# new_design.net
KiCad netlist of a schematic drawn in EAGLE
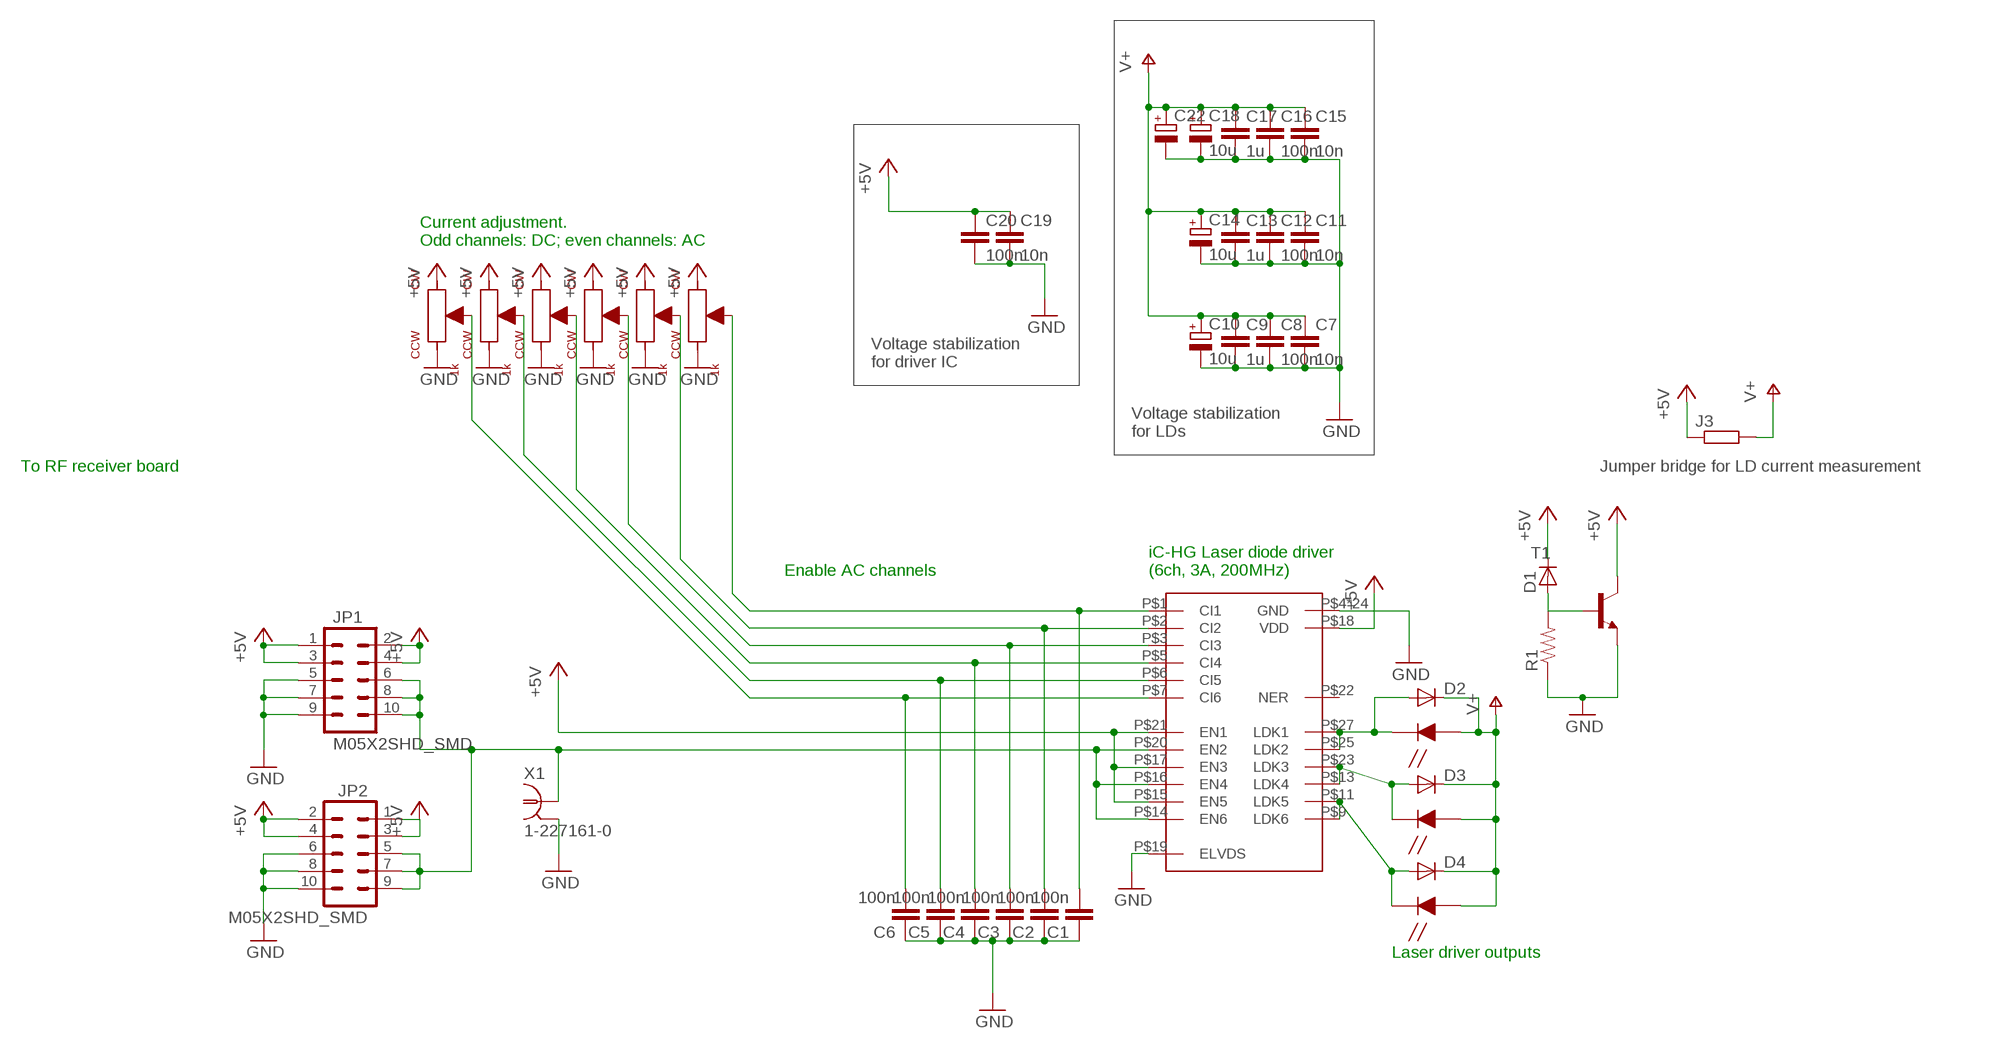
[diagram p0: schematic, sheet 1]

(export (version "E")
  (design (tool "Eeschema 10.0.6"))
  (components
    (comp (ref "C1")
      (value "100n")
      (footprint "eagle-import:C0402K")
      (libsource (lib "eagle-import") (part "C-EUC0402K"))
    )
    (comp (ref "C2")
      (value "100n")
      (footprint "eagle-import:C0402K")
      (libsource (lib "eagle-import") (part "C-EUC0402K"))
    )
    (comp (ref "C3")
      (value "100n")
      (footprint "eagle-import:C0402K")
      (libsource (lib "eagle-import") (part "C-EUC0402K"))
    )
    (comp (ref "C4")
      (value "100n")
      (footprint "eagle-import:C0402K")
      (libsource (lib "eagle-import") (part "C-EUC0402K"))
    )
    (comp (ref "C5")
      (value "100n")
      (footprint "eagle-import:C0402K")
      (libsource (lib "eagle-import") (part "C-EUC0402K"))
    )
    (comp (ref "C6")
      (value "100n")
      (footprint "eagle-import:C0402K")
      (libsource (lib "eagle-import") (part "C-EUC0402K"))
    )
    (comp (ref "C7")
      (value "10n")
      (footprint "eagle-import:C0402K")
      (libsource (lib "eagle-import") (part "C-EUC0402K"))
    )
    (comp (ref "C8")
      (value "100n")
      (footprint "eagle-import:C0402K")
      (libsource (lib "eagle-import") (part "C-EUC0402K"))
    )
    (comp (ref "C9")
      (value "1u")
      (footprint "eagle-import:C0603")
      (libsource (lib "eagle-import") (part "C-EUC0603"))
    )
    (comp (ref "C10")
      (value "10u")
      (footprint "eagle-import:SMC_B")
      (libsource (lib "eagle-import") (part "CPOL-EUSMCB"))
    )
    (comp (ref "C11")
      (value "10n")
      (footprint "eagle-import:C0402K")
      (libsource (lib "eagle-import") (part "C-EUC0402K"))
    )
    (comp (ref "C12")
      (value "100n")
      (footprint "eagle-import:C0402K")
      (libsource (lib "eagle-import") (part "C-EUC0402K"))
    )
    (comp (ref "C13")
      (value "1u")
      (footprint "eagle-import:C0603")
      (libsource (lib "eagle-import") (part "C-EUC0603"))
    )
    (comp (ref "C14")
      (value "10u")
      (footprint "eagle-import:SMC_B")
      (libsource (lib "eagle-import") (part "CPOL-EUSMCB"))
    )
    (comp (ref "C15")
      (value "10n")
      (footprint "eagle-import:C0402K")
      (libsource (lib "eagle-import") (part "C-EUC0402K"))
    )
    (comp (ref "C16")
      (value "100n")
      (footprint "eagle-import:C0402K")
      (libsource (lib "eagle-import") (part "C-EUC0402K"))
    )
    (comp (ref "C17")
      (value "1u")
      (footprint "eagle-import:C0603")
      (libsource (lib "eagle-import") (part "C-EUC0603"))
    )
    (comp (ref "C18")
      (value "10u")
      (footprint "eagle-import:SMC_B")
      (libsource (lib "eagle-import") (part "CPOL-EUSMCB"))
    )
    (comp (ref "C19")
      (value "10n")
      (footprint "eagle-import:C0402K")
      (libsource (lib "eagle-import") (part "C-EUC0402K"))
    )
    (comp (ref "C20")
      (value "100n")
      (footprint "eagle-import:C0402K")
      (libsource (lib "eagle-import") (part "C-EUC0402K"))
    )
    (comp (ref "C22")
      (value "CPOL-EUCT7343")
      (footprint "eagle-import:CT7343")
      (libsource (lib "eagle-import") (part "CPOL-EUCT7343"))
    )
    (comp (ref "D1")
      (value "D-SMB")
      (footprint "eagle-import:SMB")
      (libsource (lib "eagle-import") (part "D-SMB"))
    )
    (comp (ref "D2")
      (value "DIODE-SOD523")
      (footprint "eagle-import:SOD523")
      (libsource (lib "eagle-import") (part "DIODE-SOD523"))
    )
    (comp (ref "D3")
      (value "DIODE-SOD523")
      (footprint "eagle-import:SOD523")
      (libsource (lib "eagle-import") (part "DIODE-SOD523"))
    )
    (comp (ref "D4")
      (value "DIODE-SOD523")
      (footprint "eagle-import:SOD523")
      (libsource (lib "eagle-import") (part "DIODE-SOD523"))
    )
    (comp (ref "IC1")
      (value "IC-HGTHERMAL")
      (footprint "eagle-import:QFN28-PAD")
      (libsource (lib "eagle-import") (part "IC-HGTHERMAL"))
    )
    (comp (ref "J3")
      (value "R-EU_R1210")
      (footprint "eagle-import:R1210")
      (libsource (lib "eagle-import") (part "R-EU_R1210"))
    )
    (comp (ref "JP1")
      (value "M05X2SHD_SMD")
      (footprint "eagle-import:2X5-SHROUDED_SMD")
      (libsource (lib "eagle-import") (part "M05X2SHD_SMD"))
    )
    (comp (ref "JP2")
      (value "M05X2SHD_SMD")
      (footprint "eagle-import:2X5-SHROUDED_SMD")
      (libsource (lib "eagle-import") (part "M05X2SHD_SMD"))
    )
    (comp (ref "LD1")
      (value "LASER")
      (footprint "eagle-import:LD-FLAT")
      (libsource (lib "eagle-import") (part "LASER"))
    )
    (comp (ref "LD2")
      (value "LASER")
      (footprint "eagle-import:LD-FLAT")
      (libsource (lib "eagle-import") (part "LASER"))
    )
    (comp (ref "LD3")
      (value "LASER")
      (footprint "eagle-import:LD-FLAT")
      (libsource (lib "eagle-import") (part "LASER"))
    )
    (comp (ref "P1")
      (value "1k")
      (footprint "eagle-import:EVM-1D")
      (libsource (lib "eagle-import") (part "TRIMMERPANASONIC_EVM1D"))
    )
    (comp (ref "P2")
      (value "1k")
      (footprint "eagle-import:EVM-1D")
      (libsource (lib "eagle-import") (part "TRIMMERPANASONIC_EVM1D"))
    )
    (comp (ref "P3")
      (value "1k")
      (footprint "eagle-import:EVM-1D")
      (libsource (lib "eagle-import") (part "TRIMMERPANASONIC_EVM1D"))
    )
    (comp (ref "P4")
      (value "1k")
      (footprint "eagle-import:EVM-1D")
      (libsource (lib "eagle-import") (part "TRIMMERPANASONIC_EVM1D"))
    )
    (comp (ref "P5")
      (value "1k")
      (footprint "eagle-import:EVM-1D")
      (libsource (lib "eagle-import") (part "TRIMMERPANASONIC_EVM1D"))
    )
    (comp (ref "P6")
      (value "1k")
      (footprint "eagle-import:EVM-1D")
      (libsource (lib "eagle-import") (part "TRIMMERPANASONIC_EVM1D"))
    )
    (comp (ref "R1")
      (value "RESISTOR0805-RES")
      (footprint "eagle-import:0805")
      (libsource (lib "eagle-import") (part "RESISTOR0805-RES"))
    )
    (comp (ref "T1")
      (value "-NPN-SOT223")
      (footprint "eagle-import:SOT223")
      (libsource (lib "eagle-import") (part "-NPN-SOT223"))
    )
    (comp (ref "X1")
      (value "1-227161-0")
      (footprint "eagle-import:AMP_227161")
      (fields (field (name "MF") "TYCO ELECTRONICS") (field (name "MPN") "1-227161"))
      (libsource (lib "eagle-import") (part "?2271611--0"))
    )
  )
  (nets
    (net (code "1") (name "+5V") (class "Default")
      (node (ref "C19") (pin "1") (pinfunction "1_1") (pintype "passive"))
      (node (ref "C20") (pin "1") (pinfunction "1_1") (pintype "passive"))
      (node (ref "D1") (pin "1") (pinfunction "C_1") (pintype "passive"))
      (node (ref "IC1") (pin "P$15") (pinfunction "EN5_P$15") (pintype "input"))
      (node (ref "IC1") (pin "P$17") (pinfunction "EN3_P$17") (pintype "input"))
      (node (ref "IC1") (pin "P$18") (pinfunction "VDD_P$18") (pintype "power_in"))
      (node (ref "IC1") (pin "P$21") (pinfunction "EN1_P$21") (pintype "input"))
      (node (ref "J3") (pin "1") (pinfunction "1_1") (pintype "passive"))
      (node (ref "JP1") (pin "1") (pinfunction "1_1") (pintype "passive"))
      (node (ref "JP1") (pin "2") (pinfunction "2_2") (pintype "passive"))
      (node (ref "JP1") (pin "3") (pinfunction "3_3") (pintype "passive"))
      (node (ref "JP1") (pin "4") (pinfunction "4_4") (pintype "passive"))
      (node (ref "JP2") (pin "1") (pinfunction "1_1") (pintype "passive"))
      (node (ref "JP2") (pin "2") (pinfunction "2_2") (pintype "passive"))
      (node (ref "JP2") (pin "3") (pinfunction "3_3") (pintype "passive"))
      (node (ref "JP2") (pin "4") (pinfunction "4_4") (pintype "passive"))
      (node (ref "P1") (pin "CW") (pinfunction "CW_CW") (pintype "output"))
      (node (ref "P2") (pin "CW") (pinfunction "CW_CW") (pintype "output"))
      (node (ref "P3") (pin "CW") (pinfunction "CW_CW") (pintype "output"))
      (node (ref "P4") (pin "CW") (pinfunction "CW_CW") (pintype "output"))
      (node (ref "P5") (pin "CW") (pinfunction "CW_CW") (pintype "output"))
      (node (ref "P6") (pin "CW") (pinfunction "CW_CW") (pintype "output"))
      (node (ref "T1") (pin "4") (pinfunction "C_4") (pintype "passive"))
    )
    (net (code "2") (name "GND") (class "Default")
      (node (ref "C1") (pin "1") (pinfunction "1_1") (pintype "passive"))
      (node (ref "C10") (pin "-") (pinfunction "-_-") (pintype "passive"))
      (node (ref "C11") (pin "2") (pinfunction "2_2") (pintype "passive"))
      (node (ref "C12") (pin "2") (pinfunction "2_2") (pintype "passive"))
      (node (ref "C13") (pin "2") (pinfunction "2_2") (pintype "passive"))
      (node (ref "C14") (pin "-") (pinfunction "-_-") (pintype "passive"))
      (node (ref "C15") (pin "2") (pinfunction "2_2") (pintype "passive"))
      (node (ref "C16") (pin "2") (pinfunction "2_2") (pintype "passive"))
      (node (ref "C17") (pin "2") (pinfunction "2_2") (pintype "passive"))
      (node (ref "C18") (pin "-") (pinfunction "-_-") (pintype "passive"))
      (node (ref "C19") (pin "2") (pinfunction "2_2") (pintype "passive"))
      (node (ref "C2") (pin "1") (pinfunction "1_1") (pintype "passive"))
      (node (ref "C20") (pin "2") (pinfunction "2_2") (pintype "passive"))
      (node (ref "C22") (pin "-") (pinfunction "-_-") (pintype "passive"))
      (node (ref "C3") (pin "1") (pinfunction "1_1") (pintype "passive"))
      (node (ref "C4") (pin "1") (pinfunction "1_1") (pintype "passive"))
      (node (ref "C5") (pin "1") (pinfunction "1_1") (pintype "passive"))
      (node (ref "C6") (pin "1") (pinfunction "1_1") (pintype "passive"))
      (node (ref "C7") (pin "2") (pinfunction "2_2") (pintype "passive"))
      (node (ref "C8") (pin "2") (pinfunction "2_2") (pintype "passive"))
      (node (ref "C9") (pin "2") (pinfunction "2_2") (pintype "passive"))
      (node (ref "IC1") (pin "P$10") (pinfunction "GND_P$10") (pintype "power_in"))
      (node (ref "IC1") (pin "P$12") (pinfunction "GND_P$12") (pintype "power_in"))
      (node (ref "IC1") (pin "P$19") (pinfunction "ELVDS_P$19") (pintype "output"))
      (node (ref "IC1") (pin "P$24") (pinfunction "GND_P$24") (pintype "power_in"))
      (node (ref "IC1") (pin "P$26") (pinfunction "GND_P$26") (pintype "power_in"))
      (node (ref "IC1") (pin "P$28") (pinfunction "GND_P$28") (pintype "power_in"))
      (node (ref "IC1") (pin "P$29") (pinfunction "GND_P$29") (pintype "power_in"))
      (node (ref "IC1") (pin "P$30") (pinfunction "GND_P$30") (pintype "power_in"))
      (node (ref "IC1") (pin "P$31") (pinfunction "GND_P$31") (pintype "power_in"))
      (node (ref "IC1") (pin "P$32") (pinfunction "GND_P$32") (pintype "power_in"))
      (node (ref "IC1") (pin "P$33") (pinfunction "GND_P$33") (pintype "power_in"))
      (node (ref "IC1") (pin "P$34") (pinfunction "GND_P$34") (pintype "power_in"))
      (node (ref "IC1") (pin "P$35") (pinfunction "GND_P$35") (pintype "power_in"))
      (node (ref "IC1") (pin "P$36") (pinfunction "GND_P$36") (pintype "power_in"))
      (node (ref "IC1") (pin "P$37") (pinfunction "GND_P$37") (pintype "power_in"))
      (node (ref "IC1") (pin "P$38") (pinfunction "GND_P$38") (pintype "power_in"))
      (node (ref "IC1") (pin "P$39") (pinfunction "GND_P$39") (pintype "power_in"))
      (node (ref "IC1") (pin "P$4") (pinfunction "GND_P$4") (pintype "power_in"))
      (node (ref "IC1") (pin "P$40") (pinfunction "GND_P$40") (pintype "power_in"))
      (node (ref "IC1") (pin "P$41") (pinfunction "GND_P$41") (pintype "power_in"))
      (node (ref "IC1") (pin "P$42") (pinfunction "GND_P$42") (pintype "power_in"))
      (node (ref "IC1") (pin "P$43") (pinfunction "GND_P$43") (pintype "power_in"))
      (node (ref "IC1") (pin "P$44") (pinfunction "GND_P$44") (pintype "power_in"))
      (node (ref "IC1") (pin "P$45") (pinfunction "GND_P$45") (pintype "power_in"))
      (node (ref "IC1") (pin "P$8") (pinfunction "GND_P$8") (pintype "power_in"))
      (node (ref "JP1") (pin "5") (pinfunction "5_5") (pintype "passive"))
      (node (ref "JP1") (pin "7") (pinfunction "7_7") (pintype "passive"))
      (node (ref "JP1") (pin "9") (pinfunction "9_9") (pintype "passive"))
      (node (ref "JP2") (pin "10") (pinfunction "10_10") (pintype "passive"))
      (node (ref "JP2") (pin "6") (pinfunction "6_6") (pintype "passive"))
      (node (ref "JP2") (pin "8") (pinfunction "8_8") (pintype "passive"))
      (node (ref "P1") (pin "CCW") (pinfunction "CCW_CCW") (pintype "output"))
      (node (ref "P2") (pin "CCW") (pinfunction "CCW_CCW") (pintype "output"))
      (node (ref "P3") (pin "CCW") (pinfunction "CCW_CCW") (pintype "output"))
      (node (ref "P4") (pin "CCW") (pinfunction "CCW_CCW") (pintype "output"))
      (node (ref "P5") (pin "CCW") (pinfunction "CCW_CCW") (pintype "output"))
      (node (ref "P6") (pin "CCW") (pinfunction "CCW_CCW") (pintype "output"))
      (node (ref "R1") (pin "1") (pinfunction "1_1") (pintype "passive"))
      (node (ref "T1") (pin "3") (pinfunction "E_3") (pintype "passive"))
      (node (ref "X1") (pin "2") (pinfunction "2_2") (pintype "passive"))
    )
    (net (code "3") (name "Net-(D1-A)") (class "Default")
      (node (ref "D1") (pin "2") (pinfunction "A_2") (pintype "passive"))
      (node (ref "R1") (pin "2") (pinfunction "2_2") (pintype "passive"))
      (node (ref "T1") (pin "1") (pinfunction "B_1") (pintype "passive"))
    )
    (net (code "4") (name "Net-(IC1-CI1)") (class "Default")
      (node (ref "C1") (pin "2") (pinfunction "2_2") (pintype "passive"))
      (node (ref "IC1") (pin "P$1") (pinfunction "CI1_P$1") (pintype "input"))
      (node (ref "P1") (pin "W") (pinfunction "W_W") (pintype "output"))
    )
    (net (code "5") (name "Net-(IC1-CI2)") (class "Default")
      (node (ref "C2") (pin "2") (pinfunction "2_2") (pintype "passive"))
      (node (ref "IC1") (pin "P$2") (pinfunction "CI2_P$2") (pintype "input"))
      (node (ref "P2") (pin "W") (pinfunction "W_W") (pintype "output"))
    )
    (net (code "6") (name "Net-(IC1-CI3)") (class "Default")
      (node (ref "C3") (pin "2") (pinfunction "2_2") (pintype "passive"))
      (node (ref "IC1") (pin "P$3") (pinfunction "CI3_P$3") (pintype "input"))
      (node (ref "P3") (pin "W") (pinfunction "W_W") (pintype "output"))
    )
    (net (code "7") (name "Net-(IC1-CI4)") (class "Default")
      (node (ref "C4") (pin "2") (pinfunction "2_2") (pintype "passive"))
      (node (ref "IC1") (pin "P$5") (pinfunction "CI4_P$5") (pintype "input"))
      (node (ref "P4") (pin "W") (pinfunction "W_W") (pintype "output"))
    )
    (net (code "8") (name "Net-(IC1-CI5)") (class "Default")
      (node (ref "C5") (pin "2") (pinfunction "2_2") (pintype "passive"))
      (node (ref "IC1") (pin "P$6") (pinfunction "CI5_P$6") (pintype "input"))
      (node (ref "P5") (pin "W") (pinfunction "W_W") (pintype "output"))
    )
    (net (code "9") (name "Net-(IC1-CI6)") (class "Default")
      (node (ref "C6") (pin "2") (pinfunction "2_2") (pintype "passive"))
      (node (ref "IC1") (pin "P$7") (pinfunction "CI6_P$7") (pintype "input"))
      (node (ref "P6") (pin "W") (pinfunction "W_W") (pintype "output"))
    )
    (net (code "10") (name "Net-(IC1-EN2)") (class "Default")
      (node (ref "IC1") (pin "P$14") (pinfunction "EN6_P$14") (pintype "input"))
      (node (ref "IC1") (pin "P$16") (pinfunction "EN4_P$16") (pintype "input"))
      (node (ref "IC1") (pin "P$20") (pinfunction "EN2_P$20") (pintype "input"))
      (node (ref "JP1") (pin "10") (pinfunction "10_10") (pintype "passive"))
      (node (ref "JP1") (pin "6") (pinfunction "6_6") (pintype "passive"))
      (node (ref "JP1") (pin "8") (pinfunction "8_8") (pintype "passive"))
      (node (ref "JP2") (pin "5") (pinfunction "5_5") (pintype "passive"))
      (node (ref "JP2") (pin "7") (pinfunction "7_7") (pintype "passive"))
      (node (ref "JP2") (pin "9") (pinfunction "9_9") (pintype "passive"))
      (node (ref "X1") (pin "1") (pinfunction "1_1") (pintype "passive"))
    )
    (net (code "11") (name "Net-(IC1-LDK1)") (class "Default")
      (node (ref "D2") (pin "A") (pinfunction "A_A") (pintype "passive"))
      (node (ref "IC1") (pin "P$25") (pinfunction "LDK2_P$25") (pintype "output"))
      (node (ref "IC1") (pin "P$27") (pinfunction "LDK1_P$27") (pintype "output"))
      (node (ref "LD1") (pin "C") (pinfunction "C_C") (pintype "output"))
    )
    (net (code "12") (name "Net-(IC1-LDK3)") (class "Default")
      (node (ref "D3") (pin "A") (pinfunction "A_A") (pintype "passive"))
      (node (ref "IC1") (pin "P$13") (pinfunction "LDK4_P$13") (pintype "output"))
      (node (ref "IC1") (pin "P$23") (pinfunction "LDK3_P$23") (pintype "output"))
      (node (ref "LD2") (pin "C") (pinfunction "C_C") (pintype "output"))
    )
    (net (code "13") (name "Net-(IC1-LDK5)") (class "Default")
      (node (ref "D4") (pin "A") (pinfunction "A_A") (pintype "passive"))
      (node (ref "IC1") (pin "P$11") (pinfunction "LDK5_P$11") (pintype "output"))
      (node (ref "IC1") (pin "P$9") (pinfunction "LDK6_P$9") (pintype "output"))
      (node (ref "LD3") (pin "C") (pinfunction "C_C") (pintype "output"))
    )
    (net (code "14") (name "V+") (class "Default")
      (node (ref "C10") (pin "+") (pinfunction "+_+") (pintype "passive"))
      (node (ref "C11") (pin "1") (pinfunction "1_1") (pintype "passive"))
      (node (ref "C12") (pin "1") (pinfunction "1_1") (pintype "passive"))
      (node (ref "C13") (pin "1") (pinfunction "1_1") (pintype "passive"))
      (node (ref "C14") (pin "+") (pinfunction "+_+") (pintype "passive"))
      (node (ref "C15") (pin "1") (pinfunction "1_1") (pintype "passive"))
      (node (ref "C16") (pin "1") (pinfunction "1_1") (pintype "passive"))
      (node (ref "C17") (pin "1") (pinfunction "1_1") (pintype "passive"))
      (node (ref "C18") (pin "+") (pinfunction "+_+") (pintype "passive"))
      (node (ref "C22") (pin "+") (pinfunction "+_+") (pintype "passive"))
      (node (ref "C7") (pin "1") (pinfunction "1_1") (pintype "passive"))
      (node (ref "C8") (pin "1") (pinfunction "1_1") (pintype "passive"))
      (node (ref "C9") (pin "1") (pinfunction "1_1") (pintype "passive"))
      (node (ref "D2") (pin "C") (pinfunction "C_C") (pintype "passive"))
      (node (ref "D3") (pin "C") (pinfunction "C_C") (pintype "passive"))
      (node (ref "D4") (pin "C") (pinfunction "C_C") (pintype "passive"))
      (node (ref "J3") (pin "2") (pinfunction "2_2") (pintype "passive"))
      (node (ref "LD1") (pin "A") (pinfunction "A_A") (pintype "output"))
      (node (ref "LD2") (pin "A") (pinfunction "A_A") (pintype "output"))
      (node (ref "LD3") (pin "A") (pinfunction "A_A") (pintype "output"))
    )
    (net (code "15") (name "unconnected-(IC1-NER-PadP$22)") (class "Default")
      (node (ref "IC1") (pin "P$22") (pinfunction "NER_P$22") (pintype "output"))
    )
  )
)
